# Sheet7.net
KiCad netlist of a schematic drawn in Altium Designer
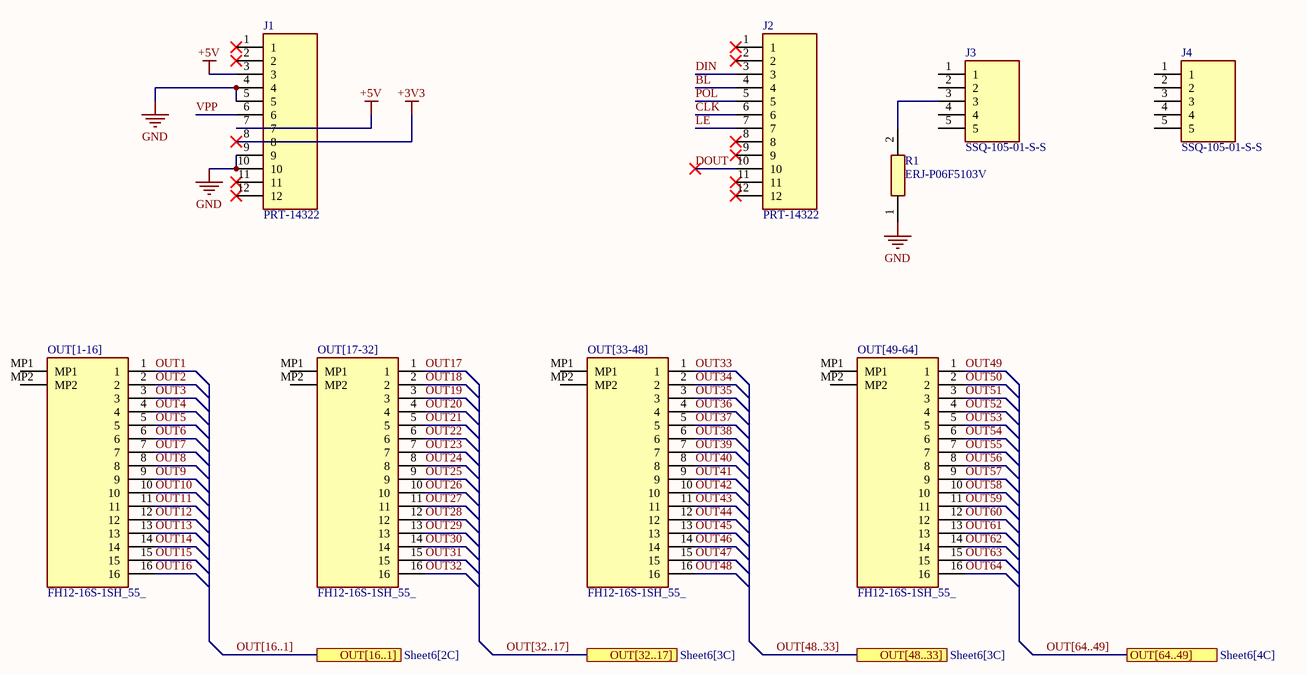
[diagram p0: Sheet7.SchDoc]

(export (version "E")
  (design (tool "Eeschema 10.0.6"))
  (components
    (comp (ref "J1")
      (value "PRT-14322")
      (footprint "RHDR12W87P0X254_1X12_3103X250X865P")
      (description "SparkFun Accessories Photon Stackable Header- 12 Pin")
      (fields (field (name "MOUSER PART NUMBER") "474-PRT-14322"))
      (libsource (lib "PRT-14322") (part "PRT-14322"))
    )
    (comp (ref "J2")
      (value "PRT-14322")
      (footprint "RHDR12W87P0X254_1X12_3103X250X865P")
      (description "SparkFun Accessories Photon Stackable Header- 12 Pin")
      (fields (field (name "MOUSER PART NUMBER") "474-PRT-14322"))
      (libsource (lib "PRT-14322") (part "PRT-14322"))
    )
    (comp (ref "J3")
      (value "SSQ-105-01-S-S")
      (footprint "RHDR5W64P254_1X5_1321X241X851P")
      (description "5 Position, .100&quot; Tiger Buy&trade; Socket Strip, Square Tail, Single Row")
      (fields (field (name "MOUSER PART NUMBER") "200-SSQ10501SS"))
      (libsource (lib "SSQ-105-01-S-S") (part "SSQ-105-01-S-S"))
    )
    (comp (ref "J4")
      (value "SSQ-105-01-S-S")
      (footprint "RHDR5W64P254_1X5_1321X241X851P")
      (description "5 Position, .100&quot; Tiger Buy&trade; Socket Strip, Square Tail, Single Row")
      (fields (field (name "MOUSER PART NUMBER") "200-SSQ10501SS"))
      (libsource (lib "SSQ-105-01-S-S") (part "SSQ-105-01-S-S"))
    )
    (comp (ref "OUT[1-16]")
      (value "FH12-16S-1SH_55_")
      (footprint "SamacSys:FH1216S1SH55")
      (description "Connector")
      (fields
        (field (name "MANUFACTURER_PART_NUMBER") "FH12-16S-1SH(55)")
        (field (name "MOUSER PART NUMBER") "798-FH12-16S-1SH55")
      )
      (libsource (lib "SamacSys") (part "FH12-16S-1SH_55_"))
    )
    (comp (ref "OUT[17-32]")
      (value "FH12-16S-1SH_55_")
      (footprint "SamacSys:FH1216S1SH55")
      (description "Connector")
      (fields
        (field (name "MANUFACTURER_PART_NUMBER") "FH12-16S-1SH(55)")
        (field (name "MOUSER PART NUMBER") "798-FH12-16S-1SH55")
      )
      (libsource (lib "SamacSys") (part "FH12-16S-1SH_55_"))
    )
    (comp (ref "OUT[33-48]")
      (value "FH12-16S-1SH_55_")
      (footprint "SamacSys:FH1216S1SH55")
      (description "Connector")
      (fields
        (field (name "MANUFACTURER_PART_NUMBER") "FH12-16S-1SH(55)")
        (field (name "MOUSER PART NUMBER") "798-FH12-16S-1SH55")
      )
      (libsource (lib "SamacSys") (part "FH12-16S-1SH_55_"))
    )
    (comp (ref "OUT[49-64]")
      (value "FH12-16S-1SH_55_")
      (footprint "SamacSys:FH1216S1SH55")
      (description "Connector")
      (fields
        (field (name "MANUFACTURER_PART_NUMBER") "FH12-16S-1SH(55)")
        (field (name "MOUSER PART NUMBER") "798-FH12-16S-1SH55")
      )
      (libsource (lib "SamacSys") (part "FH12-16S-1SH_55_"))
    )
    (comp (ref "R1")
      (value "ERJ-P06F5103V")
      (footprint "SamacSys:ERJP06D1000V")
      (description "Resistor")
      (fields (field (name "MOUSER PART NUMBER") "667-ERJ-P06F5103V"))
      (libsource (lib "SamacSys") (part "ERJ-P06F5103V"))
    )
  )
  (nets
    (net (code "1") (name "+3V3") (class "Default")
      (node (ref "J1") (pin "8") (pinfunction "8_8") (pintype "passive"))
    )
    (net (code "2") (name "+5V") (class "Default")
      (node (ref "J1") (pin "3") (pinfunction "3_3") (pintype "passive"))
      (node (ref "J1") (pin "7") (pinfunction "7_7") (pintype "passive"))
    )
    (net (code "3") (name "/BL") (class "Default")
      (node (ref "J2") (pin "4") (pinfunction "4_4") (pintype "passive"))
    )
    (net (code "4") (name "/CLK") (class "Default")
      (node (ref "J2") (pin "6") (pinfunction "6_6") (pintype "passive"))
    )
    (net (code "5") (name "/DIN") (class "Default")
      (node (ref "J2") (pin "3") (pinfunction "3_3") (pintype "passive"))
    )
    (net (code "6") (name "/DOUT") (class "Default")
      (node (ref "J2") (pin "10") (pinfunction "10_10") (pintype "passive+no_connect"))
    )
    (net (code "7") (name "/LE") (class "Default")
      (node (ref "J2") (pin "7") (pinfunction "7_7") (pintype "passive"))
    )
    (net (code "8") (name "/OUT1") (class "Default")
      (node (ref "OUT[1-16]") (pin "1") (pinfunction "1_1") (pintype "passive"))
    )
    (net (code "9") (name "/OUT2") (class "Default")
      (node (ref "OUT[1-16]") (pin "2") (pinfunction "2_2") (pintype "passive"))
    )
    (net (code "10") (name "/OUT3") (class "Default")
      (node (ref "OUT[1-16]") (pin "3") (pinfunction "3_3") (pintype "passive"))
    )
    (net (code "11") (name "/OUT4") (class "Default")
      (node (ref "OUT[1-16]") (pin "4") (pinfunction "4_4") (pintype "passive"))
    )
    (net (code "12") (name "/OUT5") (class "Default")
      (node (ref "OUT[1-16]") (pin "5") (pinfunction "5_5") (pintype "passive"))
    )
    (net (code "13") (name "/OUT6") (class "Default")
      (node (ref "OUT[1-16]") (pin "6") (pinfunction "6_6") (pintype "passive"))
    )
    (net (code "14") (name "/OUT7") (class "Default")
      (node (ref "OUT[1-16]") (pin "7") (pinfunction "7_7") (pintype "passive"))
    )
    (net (code "15") (name "/OUT8") (class "Default")
      (node (ref "OUT[1-16]") (pin "8") (pinfunction "8_8") (pintype "passive"))
    )
    (net (code "16") (name "/OUT9") (class "Default")
      (node (ref "OUT[1-16]") (pin "9") (pinfunction "9_9") (pintype "passive"))
    )
    (net (code "17") (name "/OUT10") (class "Default")
      (node (ref "OUT[1-16]") (pin "10") (pinfunction "10_10") (pintype "passive"))
    )
    (net (code "18") (name "/OUT11") (class "Default")
      (node (ref "OUT[1-16]") (pin "11") (pinfunction "11_11") (pintype "passive"))
    )
    (net (code "19") (name "/OUT12") (class "Default")
      (node (ref "OUT[1-16]") (pin "12") (pinfunction "12_12") (pintype "passive"))
    )
    (net (code "20") (name "/OUT13") (class "Default")
      (node (ref "OUT[1-16]") (pin "13") (pinfunction "13_13") (pintype "passive"))
    )
    (net (code "21") (name "/OUT14") (class "Default")
      (node (ref "OUT[1-16]") (pin "14") (pinfunction "14_14") (pintype "passive"))
    )
    (net (code "22") (name "/OUT15") (class "Default")
      (node (ref "OUT[1-16]") (pin "15") (pinfunction "15_15") (pintype "passive"))
    )
    (net (code "23") (name "/OUT16") (class "Default")
      (node (ref "OUT[1-16]") (pin "16") (pinfunction "16_16") (pintype "passive"))
    )
    (net (code "24") (name "/OUT17") (class "Default")
      (node (ref "OUT[17-32]") (pin "1") (pinfunction "1_1") (pintype "passive"))
    )
    (net (code "25") (name "/OUT18") (class "Default")
      (node (ref "OUT[17-32]") (pin "2") (pinfunction "2_2") (pintype "passive"))
    )
    (net (code "26") (name "/OUT19") (class "Default")
      (node (ref "OUT[17-32]") (pin "3") (pinfunction "3_3") (pintype "passive"))
    )
    (net (code "27") (name "/OUT20") (class "Default")
      (node (ref "OUT[17-32]") (pin "4") (pinfunction "4_4") (pintype "passive"))
    )
    (net (code "28") (name "/OUT21") (class "Default")
      (node (ref "OUT[17-32]") (pin "5") (pinfunction "5_5") (pintype "passive"))
    )
    (net (code "29") (name "/OUT22") (class "Default")
      (node (ref "OUT[17-32]") (pin "6") (pinfunction "6_6") (pintype "passive"))
    )
    (net (code "30") (name "/OUT23") (class "Default")
      (node (ref "OUT[17-32]") (pin "7") (pinfunction "7_7") (pintype "passive"))
    )
    (net (code "31") (name "/OUT24") (class "Default")
      (node (ref "OUT[17-32]") (pin "8") (pinfunction "8_8") (pintype "passive"))
    )
    (net (code "32") (name "/OUT25") (class "Default")
      (node (ref "OUT[17-32]") (pin "9") (pinfunction "9_9") (pintype "passive"))
    )
    (net (code "33") (name "/OUT26") (class "Default")
      (node (ref "OUT[17-32]") (pin "10") (pinfunction "10_10") (pintype "passive"))
    )
    (net (code "34") (name "/OUT27") (class "Default")
      (node (ref "OUT[17-32]") (pin "11") (pinfunction "11_11") (pintype "passive"))
    )
    (net (code "35") (name "/OUT28") (class "Default")
      (node (ref "OUT[17-32]") (pin "12") (pinfunction "12_12") (pintype "passive"))
    )
    (net (code "36") (name "/OUT29") (class "Default")
      (node (ref "OUT[17-32]") (pin "13") (pinfunction "13_13") (pintype "passive"))
    )
    (net (code "37") (name "/OUT30") (class "Default")
      (node (ref "OUT[17-32]") (pin "14") (pinfunction "14_14") (pintype "passive"))
    )
    (net (code "38") (name "/OUT31") (class "Default")
      (node (ref "OUT[17-32]") (pin "15") (pinfunction "15_15") (pintype "passive"))
    )
    (net (code "39") (name "/OUT32") (class "Default")
      (node (ref "OUT[17-32]") (pin "16") (pinfunction "16_16") (pintype "passive"))
    )
    (net (code "40") (name "/OUT33") (class "Default")
      (node (ref "OUT[33-48]") (pin "1") (pinfunction "1_1") (pintype "passive"))
    )
    (net (code "41") (name "/OUT34") (class "Default")
      (node (ref "OUT[33-48]") (pin "2") (pinfunction "2_2") (pintype "passive"))
    )
    (net (code "42") (name "/OUT35") (class "Default")
      (node (ref "OUT[33-48]") (pin "3") (pinfunction "3_3") (pintype "passive"))
    )
    (net (code "43") (name "/OUT36") (class "Default")
      (node (ref "OUT[33-48]") (pin "4") (pinfunction "4_4") (pintype "passive"))
    )
    (net (code "44") (name "/OUT37") (class "Default")
      (node (ref "OUT[33-48]") (pin "5") (pinfunction "5_5") (pintype "passive"))
    )
    (net (code "45") (name "/OUT38") (class "Default")
      (node (ref "OUT[33-48]") (pin "6") (pinfunction "6_6") (pintype "passive"))
    )
    (net (code "46") (name "/OUT39") (class "Default")
      (node (ref "OUT[33-48]") (pin "7") (pinfunction "7_7") (pintype "passive"))
    )
    (net (code "47") (name "/OUT40") (class "Default")
      (node (ref "OUT[33-48]") (pin "8") (pinfunction "8_8") (pintype "passive"))
    )
    (net (code "48") (name "/OUT41") (class "Default")
      (node (ref "OUT[33-48]") (pin "9") (pinfunction "9_9") (pintype "passive"))
    )
    (net (code "49") (name "/OUT42") (class "Default")
      (node (ref "OUT[33-48]") (pin "10") (pinfunction "10_10") (pintype "passive"))
    )
    (net (code "50") (name "/OUT43") (class "Default")
      (node (ref "OUT[33-48]") (pin "11") (pinfunction "11_11") (pintype "passive"))
    )
    (net (code "51") (name "/OUT44") (class "Default")
      (node (ref "OUT[33-48]") (pin "12") (pinfunction "12_12") (pintype "passive"))
    )
    (net (code "52") (name "/OUT45") (class "Default")
      (node (ref "OUT[33-48]") (pin "13") (pinfunction "13_13") (pintype "passive"))
    )
    (net (code "53") (name "/OUT46") (class "Default")
      (node (ref "OUT[33-48]") (pin "14") (pinfunction "14_14") (pintype "passive"))
    )
    (net (code "54") (name "/OUT47") (class "Default")
      (node (ref "OUT[33-48]") (pin "15") (pinfunction "15_15") (pintype "passive"))
    )
    (net (code "55") (name "/OUT48") (class "Default")
      (node (ref "OUT[33-48]") (pin "16") (pinfunction "16_16") (pintype "passive"))
    )
    (net (code "56") (name "/OUT49") (class "Default")
      (node (ref "OUT[49-64]") (pin "1") (pinfunction "1_1") (pintype "passive"))
    )
    (net (code "57") (name "/OUT50") (class "Default")
      (node (ref "OUT[49-64]") (pin "2") (pinfunction "2_2") (pintype "passive"))
    )
    (net (code "58") (name "/OUT51") (class "Default")
      (node (ref "OUT[49-64]") (pin "3") (pinfunction "3_3") (pintype "passive"))
    )
    (net (code "59") (name "/OUT52") (class "Default")
      (node (ref "OUT[49-64]") (pin "4") (pinfunction "4_4") (pintype "passive"))
    )
    (net (code "60") (name "/OUT53") (class "Default")
      (node (ref "OUT[49-64]") (pin "5") (pinfunction "5_5") (pintype "passive"))
    )
    (net (code "61") (name "/OUT54") (class "Default")
      (node (ref "OUT[49-64]") (pin "6") (pinfunction "6_6") (pintype "passive"))
    )
    (net (code "62") (name "/OUT55") (class "Default")
      (node (ref "OUT[49-64]") (pin "7") (pinfunction "7_7") (pintype "passive"))
    )
    (net (code "63") (name "/OUT56") (class "Default")
      (node (ref "OUT[49-64]") (pin "8") (pinfunction "8_8") (pintype "passive"))
    )
    (net (code "64") (name "/OUT57") (class "Default")
      (node (ref "OUT[49-64]") (pin "9") (pinfunction "9_9") (pintype "passive"))
    )
    (net (code "65") (name "/OUT58") (class "Default")
      (node (ref "OUT[49-64]") (pin "10") (pinfunction "10_10") (pintype "passive"))
    )
    (net (code "66") (name "/OUT59") (class "Default")
      (node (ref "OUT[49-64]") (pin "11") (pinfunction "11_11") (pintype "passive"))
    )
    (net (code "67") (name "/OUT60") (class "Default")
      (node (ref "OUT[49-64]") (pin "12") (pinfunction "12_12") (pintype "passive"))
    )
    (net (code "68") (name "/OUT61") (class "Default")
      (node (ref "OUT[49-64]") (pin "13") (pinfunction "13_13") (pintype "passive"))
    )
    (net (code "69") (name "/OUT62") (class "Default")
      (node (ref "OUT[49-64]") (pin "14") (pinfunction "14_14") (pintype "passive"))
    )
    (net (code "70") (name "/OUT63") (class "Default")
      (node (ref "OUT[49-64]") (pin "15") (pinfunction "15_15") (pintype "passive"))
    )
    (net (code "71") (name "/OUT64") (class "Default")
      (node (ref "OUT[49-64]") (pin "16") (pinfunction "16_16") (pintype "passive"))
    )
    (net (code "76") (name "/POL") (class "Default")
      (node (ref "J2") (pin "5") (pinfunction "5_5") (pintype "passive"))
    )
    (net (code "77") (name "/VPP") (class "Default")
      (node (ref "J1") (pin "6") (pinfunction "6_6") (pintype "passive"))
    )
    (net (code "78") (name "GND") (class "Default")
      (node (ref "J1") (pin "10") (pinfunction "10_10") (pintype "passive"))
      (node (ref "J1") (pin "4") (pinfunction "4_4") (pintype "passive"))
      (node (ref "J1") (pin "5") (pinfunction "5_5") (pintype "passive"))
      (node (ref "J1") (pin "9") (pinfunction "9_9") (pintype "passive"))
      (node (ref "R1") (pin "1") (pinfunction "1_1") (pintype "passive"))
    )
    (net (code "79") (name "Net-(J3-Pad3)") (class "Default")
      (node (ref "J3") (pin "3") (pinfunction "3_3") (pintype "passive"))
      (node (ref "R1") (pin "2") (pinfunction "2_2") (pintype "passive"))
    )
    (net (code "80") (name "unconnected-(J1-Pad1)") (class "Default")
      (node (ref "J1") (pin "1") (pinfunction "1_1") (pintype "passive+no_connect"))
    )
    (net (code "81") (name "unconnected-(J1-Pad2)") (class "Default")
      (node (ref "J1") (pin "2") (pinfunction "2_2") (pintype "passive+no_connect"))
    )
    (net (code "82") (name "unconnected-(J1-Pad11)") (class "Default")
      (node (ref "J1") (pin "11") (pinfunction "11_11") (pintype "passive+no_connect"))
    )
    (net (code "83") (name "unconnected-(J1-Pad12)") (class "Default")
      (node (ref "J1") (pin "12") (pinfunction "12_12") (pintype "passive+no_connect"))
    )
    (net (code "84") (name "unconnected-(J2-Pad1)") (class "Default")
      (node (ref "J2") (pin "1") (pinfunction "1_1") (pintype "passive+no_connect"))
    )
    (net (code "85") (name "unconnected-(J2-Pad2)") (class "Default")
      (node (ref "J2") (pin "2") (pinfunction "2_2") (pintype "passive+no_connect"))
    )
    (net (code "86") (name "unconnected-(J2-Pad8)") (class "Default")
      (node (ref "J2") (pin "8") (pinfunction "8_8") (pintype "passive+no_connect"))
    )
    (net (code "87") (name "unconnected-(J2-Pad9)") (class "Default")
      (node (ref "J2") (pin "9") (pinfunction "9_9") (pintype "passive+no_connect"))
    )
    (net (code "88") (name "unconnected-(J2-Pad11)") (class "Default")
      (node (ref "J2") (pin "11") (pinfunction "11_11") (pintype "passive+no_connect"))
    )
    (net (code "89") (name "unconnected-(J2-Pad12)") (class "Default")
      (node (ref "J2") (pin "12") (pinfunction "12_12") (pintype "passive+no_connect"))
    )
    (net (code "90") (name "unconnected-(J3-Pad1)") (class "Default")
      (node (ref "J3") (pin "1") (pinfunction "1_1") (pintype "passive"))
    )
    (net (code "91") (name "unconnected-(J3-Pad2)") (class "Default")
      (node (ref "J3") (pin "2") (pinfunction "2_2") (pintype "passive"))
    )
    (net (code "92") (name "unconnected-(J3-Pad4)") (class "Default")
      (node (ref "J3") (pin "4") (pinfunction "4_4") (pintype "passive"))
    )
    (net (code "93") (name "unconnected-(J3-Pad5)") (class "Default")
      (node (ref "J3") (pin "5") (pinfunction "5_5") (pintype "passive"))
    )
    (net (code "94") (name "unconnected-(J4-Pad1)") (class "Default")
      (node (ref "J4") (pin "1") (pinfunction "1_1") (pintype "passive"))
    )
    (net (code "95") (name "unconnected-(J4-Pad2)") (class "Default")
      (node (ref "J4") (pin "2") (pinfunction "2_2") (pintype "passive"))
    )
    (net (code "96") (name "unconnected-(J4-Pad3)") (class "Default")
      (node (ref "J4") (pin "3") (pinfunction "3_3") (pintype "passive"))
    )
    (net (code "97") (name "unconnected-(J4-Pad4)") (class "Default")
      (node (ref "J4") (pin "4") (pinfunction "4_4") (pintype "passive"))
    )
    (net (code "98") (name "unconnected-(J4-Pad5)") (class "Default")
      (node (ref "J4") (pin "5") (pinfunction "5_5") (pintype "passive"))
    )
    (net (code "99") (name "unconnected-(OUT[1-16]-PadMP1)") (class "Default")
      (node (ref "OUT[1-16]") (pin "MP1") (pinfunction "MP1_MP1") (pintype "passive"))
    )
    (net (code "100") (name "unconnected-(OUT[1-16]-PadMP2)") (class "Default")
      (node (ref "OUT[1-16]") (pin "MP2") (pinfunction "MP2_MP2") (pintype "passive"))
    )
    (net (code "101") (name "unconnected-(OUT[17-32]-PadMP1)") (class "Default")
      (node (ref "OUT[17-32]") (pin "MP1") (pinfunction "MP1_MP1") (pintype "passive"))
    )
    (net (code "102") (name "unconnected-(OUT[17-32]-PadMP2)") (class "Default")
      (node (ref "OUT[17-32]") (pin "MP2") (pinfunction "MP2_MP2") (pintype "passive"))
    )
    (net (code "103") (name "unconnected-(OUT[33-48]-PadMP1)") (class "Default")
      (node (ref "OUT[33-48]") (pin "MP1") (pinfunction "MP1_MP1") (pintype "passive"))
    )
    (net (code "104") (name "unconnected-(OUT[33-48]-PadMP2)") (class "Default")
      (node (ref "OUT[33-48]") (pin "MP2") (pinfunction "MP2_MP2") (pintype "passive"))
    )
    (net (code "105") (name "unconnected-(OUT[49-64]-PadMP1)") (class "Default")
      (node (ref "OUT[49-64]") (pin "MP1") (pinfunction "MP1_MP1") (pintype "passive"))
    )
    (net (code "106") (name "unconnected-(OUT[49-64]-PadMP2)") (class "Default")
      (node (ref "OUT[49-64]") (pin "MP2") (pinfunction "MP2_MP2") (pintype "passive"))
    )
  )
)
